# QDRII_power.net
KiCad netlist of a schematic drawn in Altium Designer
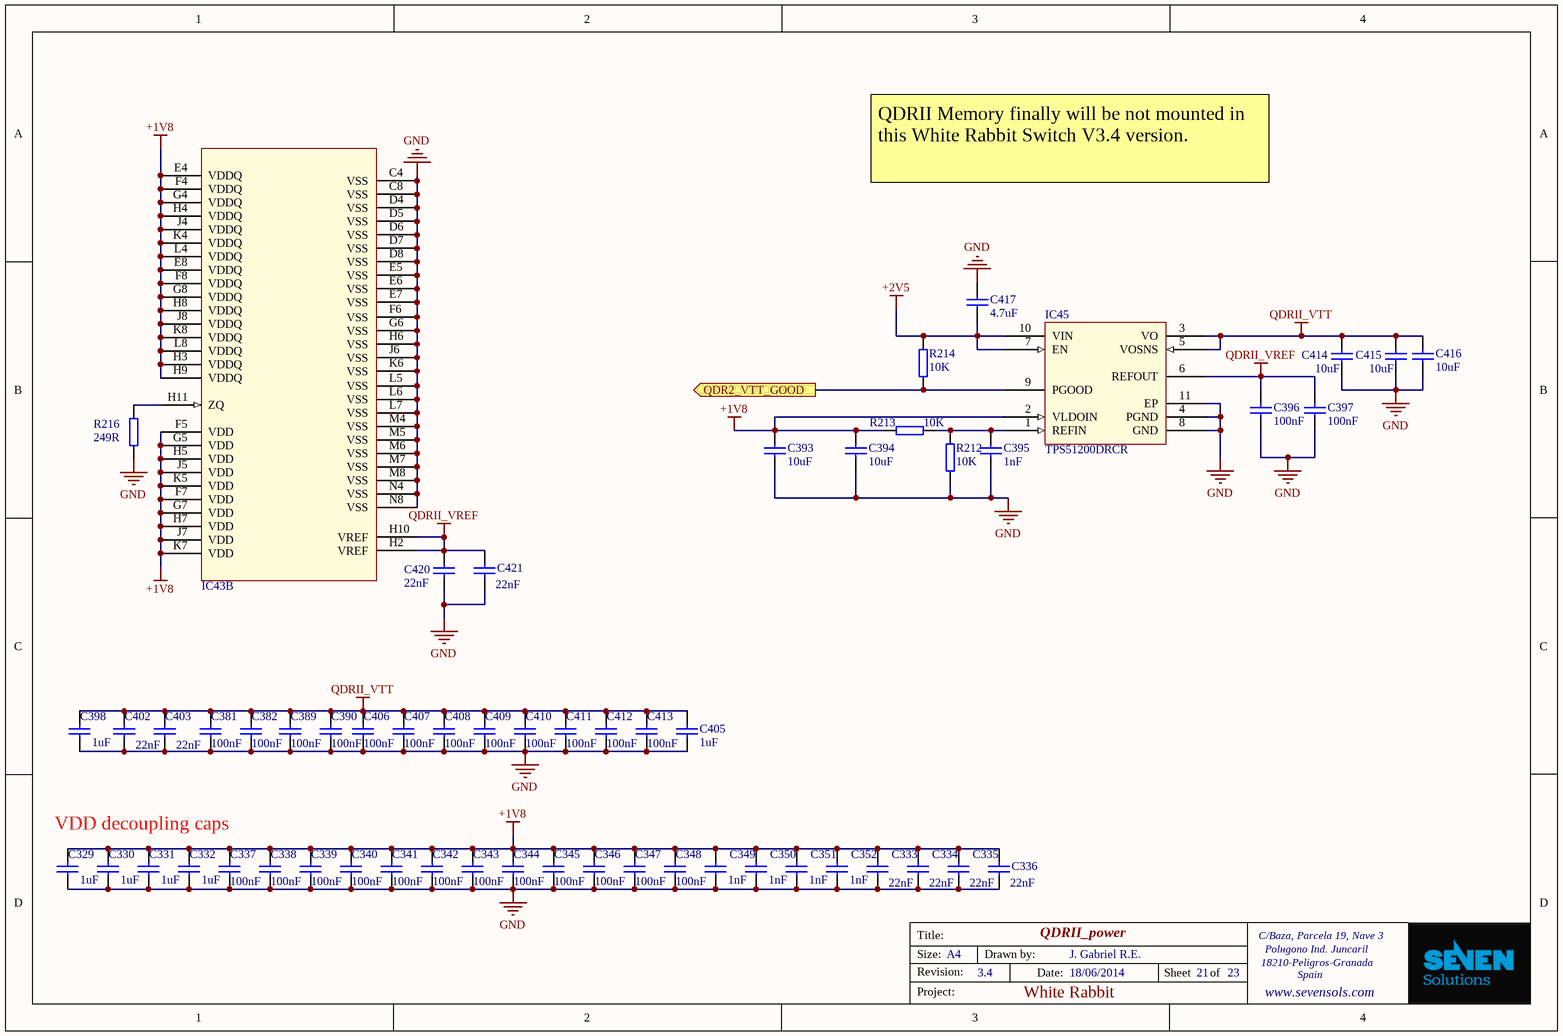
[diagram p0: QDRII_power.SchDoc]

(export (version "E")
  (design (tool "Eeschema 10.0.6"))
  (components
    (comp (ref "C329")
      (value "1uF")
      (footprint "CC1005-0402")
      (description "Capacitor")
      (fields
        (field (name "TOLERANCE") "±10%")
        (field (name "VOLTAGE") "16V")
        (field (name "PUBLISHER") "Altium Limited")
      )
      (libsource (lib "wr_switch") (part "Cap"))
    )
    (comp (ref "C330")
      (value "1uF")
      (footprint "CC1005-0402")
      (description "Capacitor")
      (fields
        (field (name "TOLERANCE") "±10%")
        (field (name "VOLTAGE") "16V")
        (field (name "PUBLISHER") "Altium Limited")
      )
      (libsource (lib "wr_switch") (part "Cap"))
    )
    (comp (ref "C331")
      (value "1uF")
      (footprint "CC1005-0402")
      (description "Capacitor")
      (fields
        (field (name "TOLERANCE") "±10%")
        (field (name "VOLTAGE") "16V")
        (field (name "PUBLISHER") "Altium Limited")
      )
      (libsource (lib "wr_switch") (part "Cap"))
    )
    (comp (ref "C332")
      (value "1uF")
      (footprint "CC1005-0402")
      (description "Capacitor")
      (fields
        (field (name "TOLERANCE") "±10%")
        (field (name "VOLTAGE") "16V")
        (field (name "PUBLISHER") "Altium Limited")
      )
      (libsource (lib "wr_switch") (part "Cap"))
    )
    (comp (ref "C333")
      (value "22nF")
      (footprint "CC1005-0402")
      (description "Capacitor")
      (fields
        (field (name "TOLERANCE") "±10%")
        (field (name "VOLTAGE") "25V")
        (field (name "PUBLISHER") "Altium Limited")
      )
      (libsource (lib "wr_switch") (part "Cap"))
    )
    (comp (ref "C334")
      (value "22nF")
      (footprint "CC1005-0402")
      (description "Capacitor")
      (fields
        (field (name "TOLERANCE") "±10%")
        (field (name "VOLTAGE") "25V")
        (field (name "PUBLISHER") "Altium Limited")
      )
      (libsource (lib "wr_switch") (part "Cap"))
    )
    (comp (ref "C335")
      (value "22nF")
      (footprint "CC1005-0402")
      (description "Capacitor")
      (fields
        (field (name "TOLERANCE") "±10%")
        (field (name "VOLTAGE") "25V")
        (field (name "PUBLISHER") "Altium Limited")
      )
      (libsource (lib "wr_switch") (part "Cap"))
    )
    (comp (ref "C336")
      (value "22nF")
      (footprint "CC1005-0402")
      (description "Capacitor")
      (fields
        (field (name "TOLERANCE") "±10%")
        (field (name "VOLTAGE") "25V")
        (field (name "PUBLISHER") "Altium Limited")
      )
      (libsource (lib "wr_switch") (part "Cap"))
    )
    (comp (ref "C337")
      (value "100nF")
      (footprint "CC1005-0402")
      (description "Capacitor")
      (fields
        (field (name "TOLERANCE") "±10%")
        (field (name "VOLTAGE") "16V")
        (field (name "PUBLISHER") "Altium Limited")
      )
      (libsource (lib "wr_switch") (part "Cap"))
    )
    (comp (ref "C338")
      (value "100nF")
      (footprint "CC1005-0402")
      (description "Capacitor")
      (fields
        (field (name "TOLERANCE") "±10%")
        (field (name "VOLTAGE") "16V")
        (field (name "PUBLISHER") "Altium Limited")
      )
      (libsource (lib "wr_switch") (part "Cap"))
    )
    (comp (ref "C339")
      (value "100nF")
      (footprint "CC1005-0402")
      (description "Capacitor")
      (fields
        (field (name "TOLERANCE") "±10%")
        (field (name "VOLTAGE") "16V")
        (field (name "PUBLISHER") "Altium Limited")
      )
      (libsource (lib "wr_switch") (part "Cap"))
    )
    (comp (ref "C340")
      (value "100nF")
      (footprint "CC1005-0402")
      (description "Capacitor")
      (fields
        (field (name "TOLERANCE") "±10%")
        (field (name "VOLTAGE") "16V")
        (field (name "PUBLISHER") "Altium Limited")
      )
      (libsource (lib "wr_switch") (part "Cap"))
    )
    (comp (ref "C341")
      (value "100nF")
      (footprint "CC1005-0402")
      (description "Capacitor")
      (fields
        (field (name "TOLERANCE") "±10%")
        (field (name "VOLTAGE") "16V")
        (field (name "PUBLISHER") "Altium Limited")
      )
      (libsource (lib "wr_switch") (part "Cap"))
    )
    (comp (ref "C342")
      (value "100nF")
      (footprint "CC1005-0402")
      (description "Capacitor")
      (fields
        (field (name "TOLERANCE") "±10%")
        (field (name "VOLTAGE") "16V")
        (field (name "PUBLISHER") "Altium Limited")
      )
      (libsource (lib "wr_switch") (part "Cap"))
    )
    (comp (ref "C343")
      (value "100nF")
      (footprint "CC1005-0402")
      (description "Capacitor")
      (fields
        (field (name "TOLERANCE") "±10%")
        (field (name "VOLTAGE") "16V")
        (field (name "PUBLISHER") "Altium Limited")
      )
      (libsource (lib "wr_switch") (part "Cap"))
    )
    (comp (ref "C344")
      (value "100nF")
      (footprint "CC1005-0402")
      (description "Capacitor")
      (fields
        (field (name "TOLERANCE") "±10%")
        (field (name "VOLTAGE") "16V")
        (field (name "PUBLISHER") "Altium Limited")
      )
      (libsource (lib "wr_switch") (part "Cap"))
    )
    (comp (ref "C345")
      (value "100nF")
      (footprint "CC1005-0402")
      (description "Capacitor")
      (fields
        (field (name "TOLERANCE") "±10%")
        (field (name "VOLTAGE") "16V")
        (field (name "PUBLISHER") "Altium Limited")
      )
      (libsource (lib "wr_switch") (part "Cap"))
    )
    (comp (ref "C346")
      (value "100nF")
      (footprint "CC1005-0402")
      (description "Capacitor")
      (fields
        (field (name "TOLERANCE") "±10%")
        (field (name "VOLTAGE") "16V")
        (field (name "PUBLISHER") "Altium Limited")
      )
      (libsource (lib "wr_switch") (part "Cap"))
    )
    (comp (ref "C347")
      (value "100nF")
      (footprint "CC1005-0402")
      (description "Capacitor")
      (fields
        (field (name "TOLERANCE") "±10%")
        (field (name "VOLTAGE") "16V")
        (field (name "PUBLISHER") "Altium Limited")
      )
      (libsource (lib "wr_switch") (part "Cap"))
    )
    (comp (ref "C348")
      (value "100nF")
      (footprint "CC1005-0402")
      (description "Capacitor")
      (fields
        (field (name "TOLERANCE") "±10%")
        (field (name "VOLTAGE") "16V")
        (field (name "PUBLISHER") "Altium Limited")
      )
      (libsource (lib "wr_switch") (part "Cap"))
    )
    (comp (ref "C349")
      (value "1nF")
      (footprint "CC1005-0402")
      (description "Capacitor")
      (fields
        (field (name "TOLERANCE") "±10%")
        (field (name "VOLTAGE") "25V")
        (field (name "PUBLISHER") "Altium Limited")
      )
      (libsource (lib "wr_switch") (part "Cap"))
    )
    (comp (ref "C350")
      (value "1nF")
      (footprint "CC1005-0402")
      (description "Capacitor")
      (fields
        (field (name "TOLERANCE") "±10%")
        (field (name "VOLTAGE") "25V")
        (field (name "PUBLISHER") "Altium Limited")
      )
      (libsource (lib "wr_switch") (part "Cap"))
    )
    (comp (ref "C351")
      (value "1nF")
      (footprint "CC1005-0402")
      (description "Capacitor")
      (fields
        (field (name "TOLERANCE") "±10%")
        (field (name "VOLTAGE") "25V")
        (field (name "PUBLISHER") "Altium Limited")
      )
      (libsource (lib "wr_switch") (part "Cap"))
    )
    (comp (ref "C352")
      (value "1nF")
      (footprint "CC1005-0402")
      (description "Capacitor")
      (fields
        (field (name "TOLERANCE") "±10%")
        (field (name "VOLTAGE") "25V")
        (field (name "PUBLISHER") "Altium Limited")
      )
      (libsource (lib "wr_switch") (part "Cap"))
    )
    (comp (ref "C381")
      (value "100nF")
      (footprint "CC1005-0402")
      (description "Capacitor")
      (fields
        (field (name "TOLERANCE") "±10%")
        (field (name "VOLTAGE") "16V")
        (field (name "PUBLISHER") "Altium Limited")
      )
      (libsource (lib "wr_switch") (part "Cap"))
    )
    (comp (ref "C382")
      (value "100nF")
      (footprint "CC1005-0402")
      (description "Capacitor")
      (fields
        (field (name "TOLERANCE") "±10%")
        (field (name "VOLTAGE") "16V")
        (field (name "PUBLISHER") "Altium Limited")
      )
      (libsource (lib "wr_switch") (part "Cap"))
    )
    (comp (ref "C389")
      (value "100nF")
      (footprint "CC1005-0402")
      (description "Capacitor")
      (fields
        (field (name "TOLERANCE") "±10%")
        (field (name "VOLTAGE") "16V")
        (field (name "PUBLISHER") "Altium Limited")
      )
      (libsource (lib "wr_switch") (part "Cap"))
    )
    (comp (ref "C390")
      (value "100nF")
      (footprint "CC1005-0402")
      (description "Capacitor")
      (fields
        (field (name "TOLERANCE") "±10%")
        (field (name "VOLTAGE") "16V")
        (field (name "PUBLISHER") "Altium Limited")
      )
      (libsource (lib "wr_switch") (part "Cap"))
    )
    (comp (ref "C393")
      (value "10uF")
      (footprint "CC1608-0603")
      (description "Capacitor")
      (fields
        (field (name "TOLERANCE") "±20%")
        (field (name "VOLTAGE") "6.3V")
        (field (name "PUBLISHER") "Altium Limited")
      )
      (libsource (lib "wr_switch") (part "Cap"))
    )
    (comp (ref "C394")
      (value "10uF")
      (footprint "CC1608-0603")
      (description "Capacitor")
      (fields
        (field (name "TOLERANCE") "±20%")
        (field (name "VOLTAGE") "6.3V")
        (field (name "PUBLISHER") "Altium Limited")
      )
      (libsource (lib "wr_switch") (part "Cap"))
    )
    (comp (ref "C395")
      (value "1nF")
      (footprint "CC1005-0402")
      (description "Capacitor")
      (fields
        (field (name "TOLERANCE") "±10%")
        (field (name "VOLTAGE") "25V")
        (field (name "PUBLISHER") "Altium Limited")
      )
      (libsource (lib "wr_switch") (part "Cap"))
    )
    (comp (ref "C396")
      (value "100nF")
      (footprint "CC1005-0402")
      (description "Capacitor")
      (fields
        (field (name "TOLERANCE") "±10%")
        (field (name "VOLTAGE") "16V")
        (field (name "PUBLISHER") "Altium Limited")
      )
      (libsource (lib "wr_switch") (part "Cap"))
    )
    (comp (ref "C397")
      (value "100nF")
      (footprint "CC1005-0402")
      (description "Capacitor")
      (fields
        (field (name "TOLERANCE") "±10%")
        (field (name "VOLTAGE") "16V")
        (field (name "PUBLISHER") "Altium Limited")
      )
      (libsource (lib "wr_switch") (part "Cap"))
    )
    (comp (ref "C398")
      (value "1uF")
      (footprint "CC1005-0402")
      (description "Capacitor")
      (fields
        (field (name "TOLERANCE") "±10%")
        (field (name "VOLTAGE") "16V")
        (field (name "PUBLISHER") "Altium Limited")
      )
      (libsource (lib "wr_switch") (part "Cap"))
    )
    (comp (ref "C402")
      (value "22nF")
      (footprint "CC1005-0402")
      (description "Capacitor")
      (fields
        (field (name "TOLERANCE") "±10%")
        (field (name "VOLTAGE") "25V")
        (field (name "PUBLISHER") "Altium Limited")
      )
      (libsource (lib "wr_switch") (part "Cap"))
    )
    (comp (ref "C403")
      (value "22nF")
      (footprint "CC1005-0402")
      (description "Capacitor")
      (fields
        (field (name "TOLERANCE") "±10%")
        (field (name "VOLTAGE") "25V")
        (field (name "PUBLISHER") "Altium Limited")
      )
      (libsource (lib "wr_switch") (part "Cap"))
    )
    (comp (ref "C405")
      (value "1uF")
      (footprint "CC1005-0402")
      (description "Capacitor")
      (fields
        (field (name "TOLERANCE") "±10%")
        (field (name "VOLTAGE") "16V")
        (field (name "PUBLISHER") "Altium Limited")
      )
      (libsource (lib "wr_switch") (part "Cap"))
    )
    (comp (ref "C406")
      (value "100nF")
      (footprint "CC1005-0402")
      (description "Capacitor")
      (fields
        (field (name "TOLERANCE") "±10%")
        (field (name "VOLTAGE") "16V")
        (field (name "PUBLISHER") "Altium Limited")
      )
      (libsource (lib "wr_switch") (part "Cap"))
    )
    (comp (ref "C407")
      (value "100nF")
      (footprint "CC1005-0402")
      (description "Capacitor")
      (fields
        (field (name "TOLERANCE") "±10%")
        (field (name "VOLTAGE") "16V")
        (field (name "PUBLISHER") "Altium Limited")
      )
      (libsource (lib "wr_switch") (part "Cap"))
    )
    (comp (ref "C408")
      (value "100nF")
      (footprint "CC1005-0402")
      (description "Capacitor")
      (fields
        (field (name "TOLERANCE") "±10%")
        (field (name "VOLTAGE") "16V")
        (field (name "PUBLISHER") "Altium Limited")
      )
      (libsource (lib "wr_switch") (part "Cap"))
    )
    (comp (ref "C409")
      (value "100nF")
      (footprint "CC1005-0402")
      (description "Capacitor")
      (fields
        (field (name "TOLERANCE") "±10%")
        (field (name "VOLTAGE") "16V")
        (field (name "PUBLISHER") "Altium Limited")
      )
      (libsource (lib "wr_switch") (part "Cap"))
    )
    (comp (ref "C410")
      (value "100nF")
      (footprint "CC1005-0402")
      (description "Capacitor")
      (fields
        (field (name "TOLERANCE") "±10%")
        (field (name "VOLTAGE") "16V")
        (field (name "PUBLISHER") "Altium Limited")
      )
      (libsource (lib "wr_switch") (part "Cap"))
    )
    (comp (ref "C411")
      (value "100nF")
      (footprint "CC1005-0402")
      (description "Capacitor")
      (fields
        (field (name "TOLERANCE") "±10%")
        (field (name "VOLTAGE") "16V")
        (field (name "PUBLISHER") "Altium Limited")
      )
      (libsource (lib "wr_switch") (part "Cap"))
    )
    (comp (ref "C412")
      (value "100nF")
      (footprint "CC1005-0402")
      (description "Capacitor")
      (fields
        (field (name "TOLERANCE") "±10%")
        (field (name "VOLTAGE") "16V")
        (field (name "PUBLISHER") "Altium Limited")
      )
      (libsource (lib "wr_switch") (part "Cap"))
    )
    (comp (ref "C413")
      (value "100nF")
      (footprint "CC1005-0402")
      (description "Capacitor")
      (fields
        (field (name "TOLERANCE") "±10%")
        (field (name "VOLTAGE") "16V")
        (field (name "PUBLISHER") "Altium Limited")
      )
      (libsource (lib "wr_switch") (part "Cap"))
    )
    (comp (ref "C414")
      (value "10uF")
      (footprint "CC1608-0603")
      (description "Capacitor")
      (fields
        (field (name "TOLERANCE") "±20%")
        (field (name "VOLTAGE") "6.3V")
        (field (name "PUBLISHER") "Altium Limited")
      )
      (libsource (lib "wr_switch") (part "Cap"))
    )
    (comp (ref "C415")
      (value "10uF")
      (footprint "CC1608-0603")
      (description "Capacitor")
      (fields
        (field (name "TOLERANCE") "±20%")
        (field (name "VOLTAGE") "6.3V")
        (field (name "PUBLISHER") "Altium Limited")
      )
      (libsource (lib "wr_switch") (part "Cap"))
    )
    (comp (ref "C416")
      (value "10uF")
      (footprint "CC1608-0603")
      (description "Capacitor")
      (fields
        (field (name "TOLERANCE") "±20%")
        (field (name "VOLTAGE") "6.3V")
        (field (name "PUBLISHER") "Altium Limited")
      )
      (libsource (lib "wr_switch") (part "Cap"))
    )
    (comp (ref "C417")
      (value "4.7uF")
      (footprint "CC1608-0603")
      (description "Capacitor")
      (fields
        (field (name "TOLERANCE") "±10%")
        (field (name "VOLTAGE") "10V")
        (field (name "PUBLISHER") "Altium Limited")
      )
      (libsource (lib "wr_switch") (part "Cap"))
    )
    (comp (ref "C420")
      (value "22nF")
      (footprint "CC1005-0402")
      (description "Capacitor")
      (fields
        (field (name "TOLERANCE") "±10%")
        (field (name "VOLTAGE") "25V")
        (field (name "PUBLISHER") "Altium Limited")
      )
      (libsource (lib "wr_switch") (part "Cap"))
    )
    (comp (ref "C421")
      (value "22nF")
      (footprint "CC1005-0402")
      (description "Capacitor")
      (fields
        (field (name "TOLERANCE") "±10%")
        (field (name "VOLTAGE") "25V")
        (field (name "PUBLISHER") "Altium Limited")
      )
      (libsource (lib "wr_switch") (part "Cap"))
    )
    (comp (ref "IC43")
      (value "CY7C1314KV18-250BZC")
      (footprint "BGA165C100P11X15_1300X1500X140")
      (description "18-Mbit (512Kx36) QDRII SRAM 2-Word Burst Architecture")
      (libsource (lib "wr_switch") (part "CY7C1314CV18"))
    )
    (comp (ref "IC45")
      (value "TPS51200DRCR")
      (footprint "SON50P300X300X100-11N-R175X250")
      (description "Sink/Source DDR Termination Regulator")
      (libsource (lib "wr_switch") (part "TPS51200"))
    )
    (comp (ref "R212")
      (value "10K")
      (footprint "0402")
      (description "SMD Resistor")
      (fields (field (name "TOLERANCE") "±1%") (field (name "Comment") "10k"))
      (libsource (lib "wr_switch") (part "RES_SMD"))
    )
    (comp (ref "R213")
      (value "10K")
      (footprint "0402")
      (description "SMD Resistor")
      (fields (field (name "TOLERANCE") "±1%") (field (name "Comment") "10k"))
      (libsource (lib "wr_switch") (part "RES_SMD"))
    )
    (comp (ref "R214")
      (value "10K")
      (footprint "0402")
      (description "SMD Resistor")
      (fields (field (name "TOLERANCE") "±1%") (field (name "Comment") "10k"))
      (libsource (lib "wr_switch") (part "RES_SMD"))
    )
    (comp (ref "R216")
      (value "249R")
      (footprint "0402")
      (description "SMD Resistor")
      (fields (field (name "TOLERANCE") "±1%"))
      (libsource (lib "wr_switch") (part "RES_SMD"))
    )
  )
  (nets
    (net (code "1") (name "+1V8") (class "Default")
      (node (ref "C329") (pin "2") (pinfunction "2_2") (pintype "passive"))
      (node (ref "C330") (pin "2") (pinfunction "2_2") (pintype "passive"))
      (node (ref "C331") (pin "2") (pinfunction "2_2") (pintype "passive"))
      (node (ref "C332") (pin "2") (pinfunction "2_2") (pintype "passive"))
      (node (ref "C333") (pin "2") (pinfunction "2_2") (pintype "passive"))
      (node (ref "C334") (pin "2") (pinfunction "2_2") (pintype "passive"))
      (node (ref "C335") (pin "2") (pinfunction "2_2") (pintype "passive"))
      (node (ref "C336") (pin "2") (pinfunction "2_2") (pintype "passive"))
      (node (ref "C337") (pin "1") (pinfunction "1_1") (pintype "passive"))
      (node (ref "C338") (pin "1") (pinfunction "1_1") (pintype "passive"))
      (node (ref "C339") (pin "1") (pinfunction "1_1") (pintype "passive"))
      (node (ref "C340") (pin "1") (pinfunction "1_1") (pintype "passive"))
      (node (ref "C341") (pin "1") (pinfunction "1_1") (pintype "passive"))
      (node (ref "C342") (pin "1") (pinfunction "1_1") (pintype "passive"))
      (node (ref "C343") (pin "1") (pinfunction "1_1") (pintype "passive"))
      (node (ref "C344") (pin "1") (pinfunction "1_1") (pintype "passive"))
      (node (ref "C345") (pin "1") (pinfunction "1_1") (pintype "passive"))
      (node (ref "C346") (pin "1") (pinfunction "1_1") (pintype "passive"))
      (node (ref "C347") (pin "1") (pinfunction "1_1") (pintype "passive"))
      (node (ref "C348") (pin "1") (pinfunction "1_1") (pintype "passive"))
      (node (ref "C349") (pin "2") (pinfunction "2_2") (pintype "passive"))
      (node (ref "C350") (pin "2") (pinfunction "2_2") (pintype "passive"))
      (node (ref "C351") (pin "2") (pinfunction "2_2") (pintype "passive"))
      (node (ref "C352") (pin "2") (pinfunction "2_2") (pintype "passive"))
      (node (ref "C393") (pin "2") (pinfunction "2_2") (pintype "passive"))
      (node (ref "C394") (pin "2") (pinfunction "2_2") (pintype "passive"))
      (node (ref "IC43") (pin "E4") (pinfunction "VDDQ_E4") (pintype "power_in"))
      (node (ref "IC43") (pin "E8") (pinfunction "VDDQ_E8") (pintype "power_in"))
      (node (ref "IC43") (pin "F4") (pinfunction "VDDQ_F4") (pintype "power_in"))
      (node (ref "IC43") (pin "F5") (pinfunction "VDD_F5") (pintype "power_in"))
      (node (ref "IC43") (pin "F7") (pinfunction "VDD_F7") (pintype "power_in"))
      (node (ref "IC43") (pin "F8") (pinfunction "VDDQ_F8") (pintype "power_in"))
      (node (ref "IC43") (pin "G4") (pinfunction "VDDQ_G4") (pintype "power_in"))
      (node (ref "IC43") (pin "G5") (pinfunction "VDD_G5") (pintype "power_in"))
      (node (ref "IC43") (pin "G7") (pinfunction "VDD_G7") (pintype "power_in"))
      (node (ref "IC43") (pin "G8") (pinfunction "VDDQ_G8") (pintype "power_in"))
      (node (ref "IC43") (pin "H3") (pinfunction "VDDQ_H3") (pintype "power_in"))
      (node (ref "IC43") (pin "H4") (pinfunction "VDDQ_H4") (pintype "power_in"))
      (node (ref "IC43") (pin "H5") (pinfunction "VDD_H5") (pintype "power_in"))
      (node (ref "IC43") (pin "H7") (pinfunction "VDD_H7") (pintype "power_in"))
      (node (ref "IC43") (pin "H8") (pinfunction "VDDQ_H8") (pintype "power_in"))
      (node (ref "IC43") (pin "H9") (pinfunction "VDDQ_H9") (pintype "power_in"))
      (node (ref "IC43") (pin "J4") (pinfunction "VDDQ_J4") (pintype "power_in"))
      (node (ref "IC43") (pin "J5") (pinfunction "VDD_J5") (pintype "power_in"))
      (node (ref "IC43") (pin "J7") (pinfunction "VDD_J7") (pintype "power_in"))
      (node (ref "IC43") (pin "J8") (pinfunction "VDDQ_J8") (pintype "power_in"))
      (node (ref "IC43") (pin "K4") (pinfunction "VDDQ_K4") (pintype "power_in"))
      (node (ref "IC43") (pin "K5") (pinfunction "VDD_K5") (pintype "power_in"))
      (node (ref "IC43") (pin "K7") (pinfunction "VDD_K7") (pintype "power_in"))
      (node (ref "IC43") (pin "K8") (pinfunction "VDDQ_K8") (pintype "power_in"))
      (node (ref "IC43") (pin "L4") (pinfunction "VDDQ_L4") (pintype "power_in"))
      (node (ref "IC43") (pin "L8") (pinfunction "VDDQ_L8") (pintype "power_in"))
      (node (ref "IC45") (pin "2") (pinfunction "VLDOIN_2") (pintype "input"))
      (node (ref "R213") (pin "2") (pinfunction "2_2") (pintype "passive"))
    )
    (net (code "2") (name "+2V5") (class "Default")
      (node (ref "C417") (pin "1") (pinfunction "1_1") (pintype "passive"))
      (node (ref "IC45") (pin "10") (pinfunction "VIN_10") (pintype "power_in"))
      (node (ref "IC45") (pin "7") (pinfunction "EN_7") (pintype "input"))
      (node (ref "R214") (pin "2") (pinfunction "2_2") (pintype "passive"))
    )
    (net (code "3") (name "/QDR2_VTT_GOOD") (class "Default")
      (node (ref "IC45") (pin "9") (pinfunction "PGOOD_9") (pintype "open_collector"))
      (node (ref "R214") (pin "1") (pinfunction "1_1") (pintype "passive"))
    )
    (net (code "4") (name "GND") (class "Default")
      (node (ref "C329") (pin "1") (pinfunction "1_1") (pintype "passive"))
      (node (ref "C330") (pin "1") (pinfunction "1_1") (pintype "passive"))
      (node (ref "C331") (pin "1") (pinfunction "1_1") (pintype "passive"))
      (node (ref "C332") (pin "1") (pinfunction "1_1") (pintype "passive"))
      (node (ref "C333") (pin "1") (pinfunction "1_1") (pintype "passive"))
      (node (ref "C334") (pin "1") (pinfunction "1_1") (pintype "passive"))
      (node (ref "C335") (pin "1") (pinfunction "1_1") (pintype "passive"))
      (node (ref "C336") (pin "1") (pinfunction "1_1") (pintype "passive"))
      (node (ref "C337") (pin "2") (pinfunction "2_2") (pintype "passive"))
      (node (ref "C338") (pin "2") (pinfunction "2_2") (pintype "passive"))
      (node (ref "C339") (pin "2") (pinfunction "2_2") (pintype "passive"))
      (node (ref "C340") (pin "2") (pinfunction "2_2") (pintype "passive"))
      (node (ref "C341") (pin "2") (pinfunction "2_2") (pintype "passive"))
      (node (ref "C342") (pin "2") (pinfunction "2_2") (pintype "passive"))
      (node (ref "C343") (pin "2") (pinfunction "2_2") (pintype "passive"))
      (node (ref "C344") (pin "2") (pinfunction "2_2") (pintype "passive"))
      (node (ref "C345") (pin "2") (pinfunction "2_2") (pintype "passive"))
      (node (ref "C346") (pin "2") (pinfunction "2_2") (pintype "passive"))
      (node (ref "C347") (pin "2") (pinfunction "2_2") (pintype "passive"))
      (node (ref "C348") (pin "2") (pinfunction "2_2") (pintype "passive"))
      (node (ref "C349") (pin "1") (pinfunction "1_1") (pintype "passive"))
      (node (ref "C350") (pin "1") (pinfunction "1_1") (pintype "passive"))
      (node (ref "C351") (pin "1") (pinfunction "1_1") (pintype "passive"))
      (node (ref "C352") (pin "1") (pinfunction "1_1") (pintype "passive"))
      (node (ref "C381") (pin "2") (pinfunction "2_2") (pintype "passive"))
      (node (ref "C382") (pin "2") (pinfunction "2_2") (pintype "passive"))
      (node (ref "C389") (pin "2") (pinfunction "2_2") (pintype "passive"))
      (node (ref "C390") (pin "2") (pinfunction "2_2") (pintype "passive"))
      (node (ref "C393") (pin "1") (pinfunction "1_1") (pintype "passive"))
      (node (ref "C394") (pin "1") (pinfunction "1_1") (pintype "passive"))
      (node (ref "C395") (pin "1") (pinfunction "1_1") (pintype "passive"))
      (node (ref "C396") (pin "2") (pinfunction "2_2") (pintype "passive"))
      (node (ref "C397") (pin "2") (pinfunction "2_2") (pintype "passive"))
      (node (ref "C398") (pin "1") (pinfunction "1_1") (pintype "passive"))
      (node (ref "C402") (pin "1") (pinfunction "1_1") (pintype "passive"))
      (node (ref "C403") (pin "1") (pinfunction "1_1") (pintype "passive"))
      (node (ref "C405") (pin "1") (pinfunction "1_1") (pintype "passive"))
      (node (ref "C406") (pin "2") (pinfunction "2_2") (pintype "passive"))
      (node (ref "C407") (pin "2") (pinfunction "2_2") (pintype "passive"))
      (node (ref "C408") (pin "2") (pinfunction "2_2") (pintype "passive"))
      (node (ref "C409") (pin "2") (pinfunction "2_2") (pintype "passive"))
      (node (ref "C410") (pin "2") (pinfunction "2_2") (pintype "passive"))
      (node (ref "C411") (pin "2") (pinfunction "2_2") (pintype "passive"))
      (node (ref "C412") (pin "2") (pinfunction "2_2") (pintype "passive"))
      (node (ref "C413") (pin "2") (pinfunction "2_2") (pintype "passive"))
      (node (ref "C414") (pin "1") (pinfunction "1_1") (pintype "passive"))
      (node (ref "C415") (pin "1") (pinfunction "1_1") (pintype "passive"))
      (node (ref "C416") (pin "1") (pinfunction "1_1") (pintype "passive"))
      (node (ref "C417") (pin "2") (pinfunction "2_2") (pintype "passive"))
      (node (ref "C420") (pin "1") (pinfunction "1_1") (pintype "passive"))
      (node (ref "C421") (pin "1") (pinfunction "1_1") (pintype "passive"))
      (node (ref "IC43") (pin "C4") (pinfunction "VSS_C4") (pintype "power_in"))
      (node (ref "IC43") (pin "C8") (pinfunction "VSS_C8") (pintype "power_in"))
      (node (ref "IC43") (pin "D4") (pinfunction "VSS_D4") (pintype "power_in"))
      (node (ref "IC43") (pin "D5") (pinfunction "VSS_D5") (pintype "power_in"))
      (node (ref "IC43") (pin "D6") (pinfunction "VSS_D6") (pintype "power_in"))
      (node (ref "IC43") (pin "D7") (pinfunction "VSS_D7") (pintype "power_in"))
      (node (ref "IC43") (pin "D8") (pinfunction "VSS_D8") (pintype "power_in"))
      (node (ref "IC43") (pin "E5") (pinfunction "VSS_E5") (pintype "power_in"))
      (node (ref "IC43") (pin "E6") (pinfunction "VSS_E6") (pintype "power_in"))
      (node (ref "IC43") (pin "E7") (pinfunction "VSS_E7") (pintype "power_in"))
      (node (ref "IC43") (pin "F6") (pinfunction "VSS_F6") (pintype "power_in"))
      (node (ref "IC43") (pin "G6") (pinfunction "VSS_G6") (pintype "power_in"))
      (node (ref "IC43") (pin "H6") (pinfunction "VSS_H6") (pintype "power_in"))
      (node (ref "IC43") (pin "J6") (pinfunction "VSS_J6") (pintype "power_in"))
      (node (ref "IC43") (pin "K6") (pinfunction "VSS_K6") (pintype "power_in"))
      (node (ref "IC43") (pin "L5") (pinfunction "VSS_L5") (pintype "power_in"))
      (node (ref "IC43") (pin "L6") (pinfunction "VSS_L6") (pintype "power_in"))
      (node (ref "IC43") (pin "L7") (pinfunction "VSS_L7") (pintype "power_in"))
      (node (ref "IC43") (pin "M4") (pinfunction "VSS_M4") (pintype "power_in"))
      (node (ref "IC43") (pin "M5") (pinfunction "VSS_M5") (pintype "power_in"))
      (node (ref "IC43") (pin "M6") (pinfunction "VSS_M6") (pintype "power_in"))
      (node (ref "IC43") (pin "M7") (pinfunction "VSS_M7") (pintype "power_in"))
      (node (ref "IC43") (pin "M8") (pinfunction "VSS_M8") (pintype "power_in"))
      (node (ref "IC43") (pin "N4") (pinfunction "VSS_N4") (pintype "power_in"))
      (node (ref "IC43") (pin "N8") (pinfunction "VSS_N8") (pintype "power_in"))
      (node (ref "IC45") (pin "11") (pinfunction "EP_11") (pintype "power_in"))
      (node (ref "IC45") (pin "4") (pinfunction "PGND_4") (pintype "power_in"))
      (node (ref "IC45") (pin "8") (pinfunction "GND_8") (pintype "power_in"))
      (node (ref "R212") (pin "1") (pinfunction "1_1") (pintype "passive"))
      (node (ref "R216") (pin "1") (pinfunction "1_1") (pintype "passive"))
    )
    (net (code "5") (name "Net-(IC43B-ZQ)") (class "Default")
      (node (ref "IC43") (pin "H11") (pinfunction "ZQ_H11") (pintype "input"))
      (node (ref "R216") (pin "2") (pinfunction "2_2") (pintype "passive"))
    )
    (net (code "6") (name "Net-(IC45-REFIN)") (class "Default")
      (node (ref "C395") (pin "2") (pinfunction "2_2") (pintype "passive"))
      (node (ref "IC45") (pin "1") (pinfunction "REFIN_1") (pintype "input"))
      (node (ref "R212") (pin "2") (pinfunction "2_2") (pintype "passive"))
      (node (ref "R213") (pin "1") (pinfunction "1_1") (pintype "passive"))
    )
    (net (code "7") (name "QDRII_VREF") (class "Default")
      (node (ref "C396") (pin "1") (pinfunction "1_1") (pintype "passive"))
      (node (ref "C397") (pin "1") (pinfunction "1_1") (pintype "passive"))
      (node (ref "C420") (pin "2") (pinfunction "2_2") (pintype "passive"))
      (node (ref "C421") (pin "2") (pinfunction "2_2") (pintype "passive"))
      (node (ref "IC43") (pin "H10") (pinfunction "VREF_H10") (pintype "power_in"))
      (node (ref "IC43") (pin "H2") (pinfunction "VREF_H2") (pintype "power_in"))
      (node (ref "IC45") (pin "6") (pinfunction "REFOUT_6") (pintype "power_in"))
    )
    (net (code "8") (name "QDRII_VTT") (class "Default")
      (node (ref "C381") (pin "1") (pinfunction "1_1") (pintype "passive"))
      (node (ref "C382") (pin "1") (pinfunction "1_1") (pintype "passive"))
      (node (ref "C389") (pin "1") (pinfunction "1_1") (pintype "passive"))
      (node (ref "C390") (pin "1") (pinfunction "1_1") (pintype "passive"))
      (node (ref "C398") (pin "2") (pinfunction "2_2") (pintype "passive"))
      (node (ref "C402") (pin "2") (pinfunction "2_2") (pintype "passive"))
      (node (ref "C403") (pin "2") (pinfunction "2_2") (pintype "passive"))
      (node (ref "C405") (pin "2") (pinfunction "2_2") (pintype "passive"))
      (node (ref "C406") (pin "1") (pinfunction "1_1") (pintype "passive"))
      (node (ref "C407") (pin "1") (pinfunction "1_1") (pintype "passive"))
      (node (ref "C408") (pin "1") (pinfunction "1_1") (pintype "passive"))
      (node (ref "C409") (pin "1") (pinfunction "1_1") (pintype "passive"))
      (node (ref "C410") (pin "1") (pinfunction "1_1") (pintype "passive"))
      (node (ref "C411") (pin "1") (pinfunction "1_1") (pintype "passive"))
      (node (ref "C412") (pin "1") (pinfunction "1_1") (pintype "passive"))
      (node (ref "C413") (pin "1") (pinfunction "1_1") (pintype "passive"))
      (node (ref "C414") (pin "2") (pinfunction "2_2") (pintype "passive"))
      (node (ref "C415") (pin "2") (pinfunction "2_2") (pintype "passive"))
      (node (ref "C416") (pin "2") (pinfunction "2_2") (pintype "passive"))
      (node (ref "IC45") (pin "3") (pinfunction "VO_3") (pintype "power_in"))
      (node (ref "IC45") (pin "5") (pinfunction "VOSNS_5") (pintype "input"))
    )
  )
)
